# rs232_24V_step_Vano.net
KiCad netlist of a schematic drawn in Altium Designer
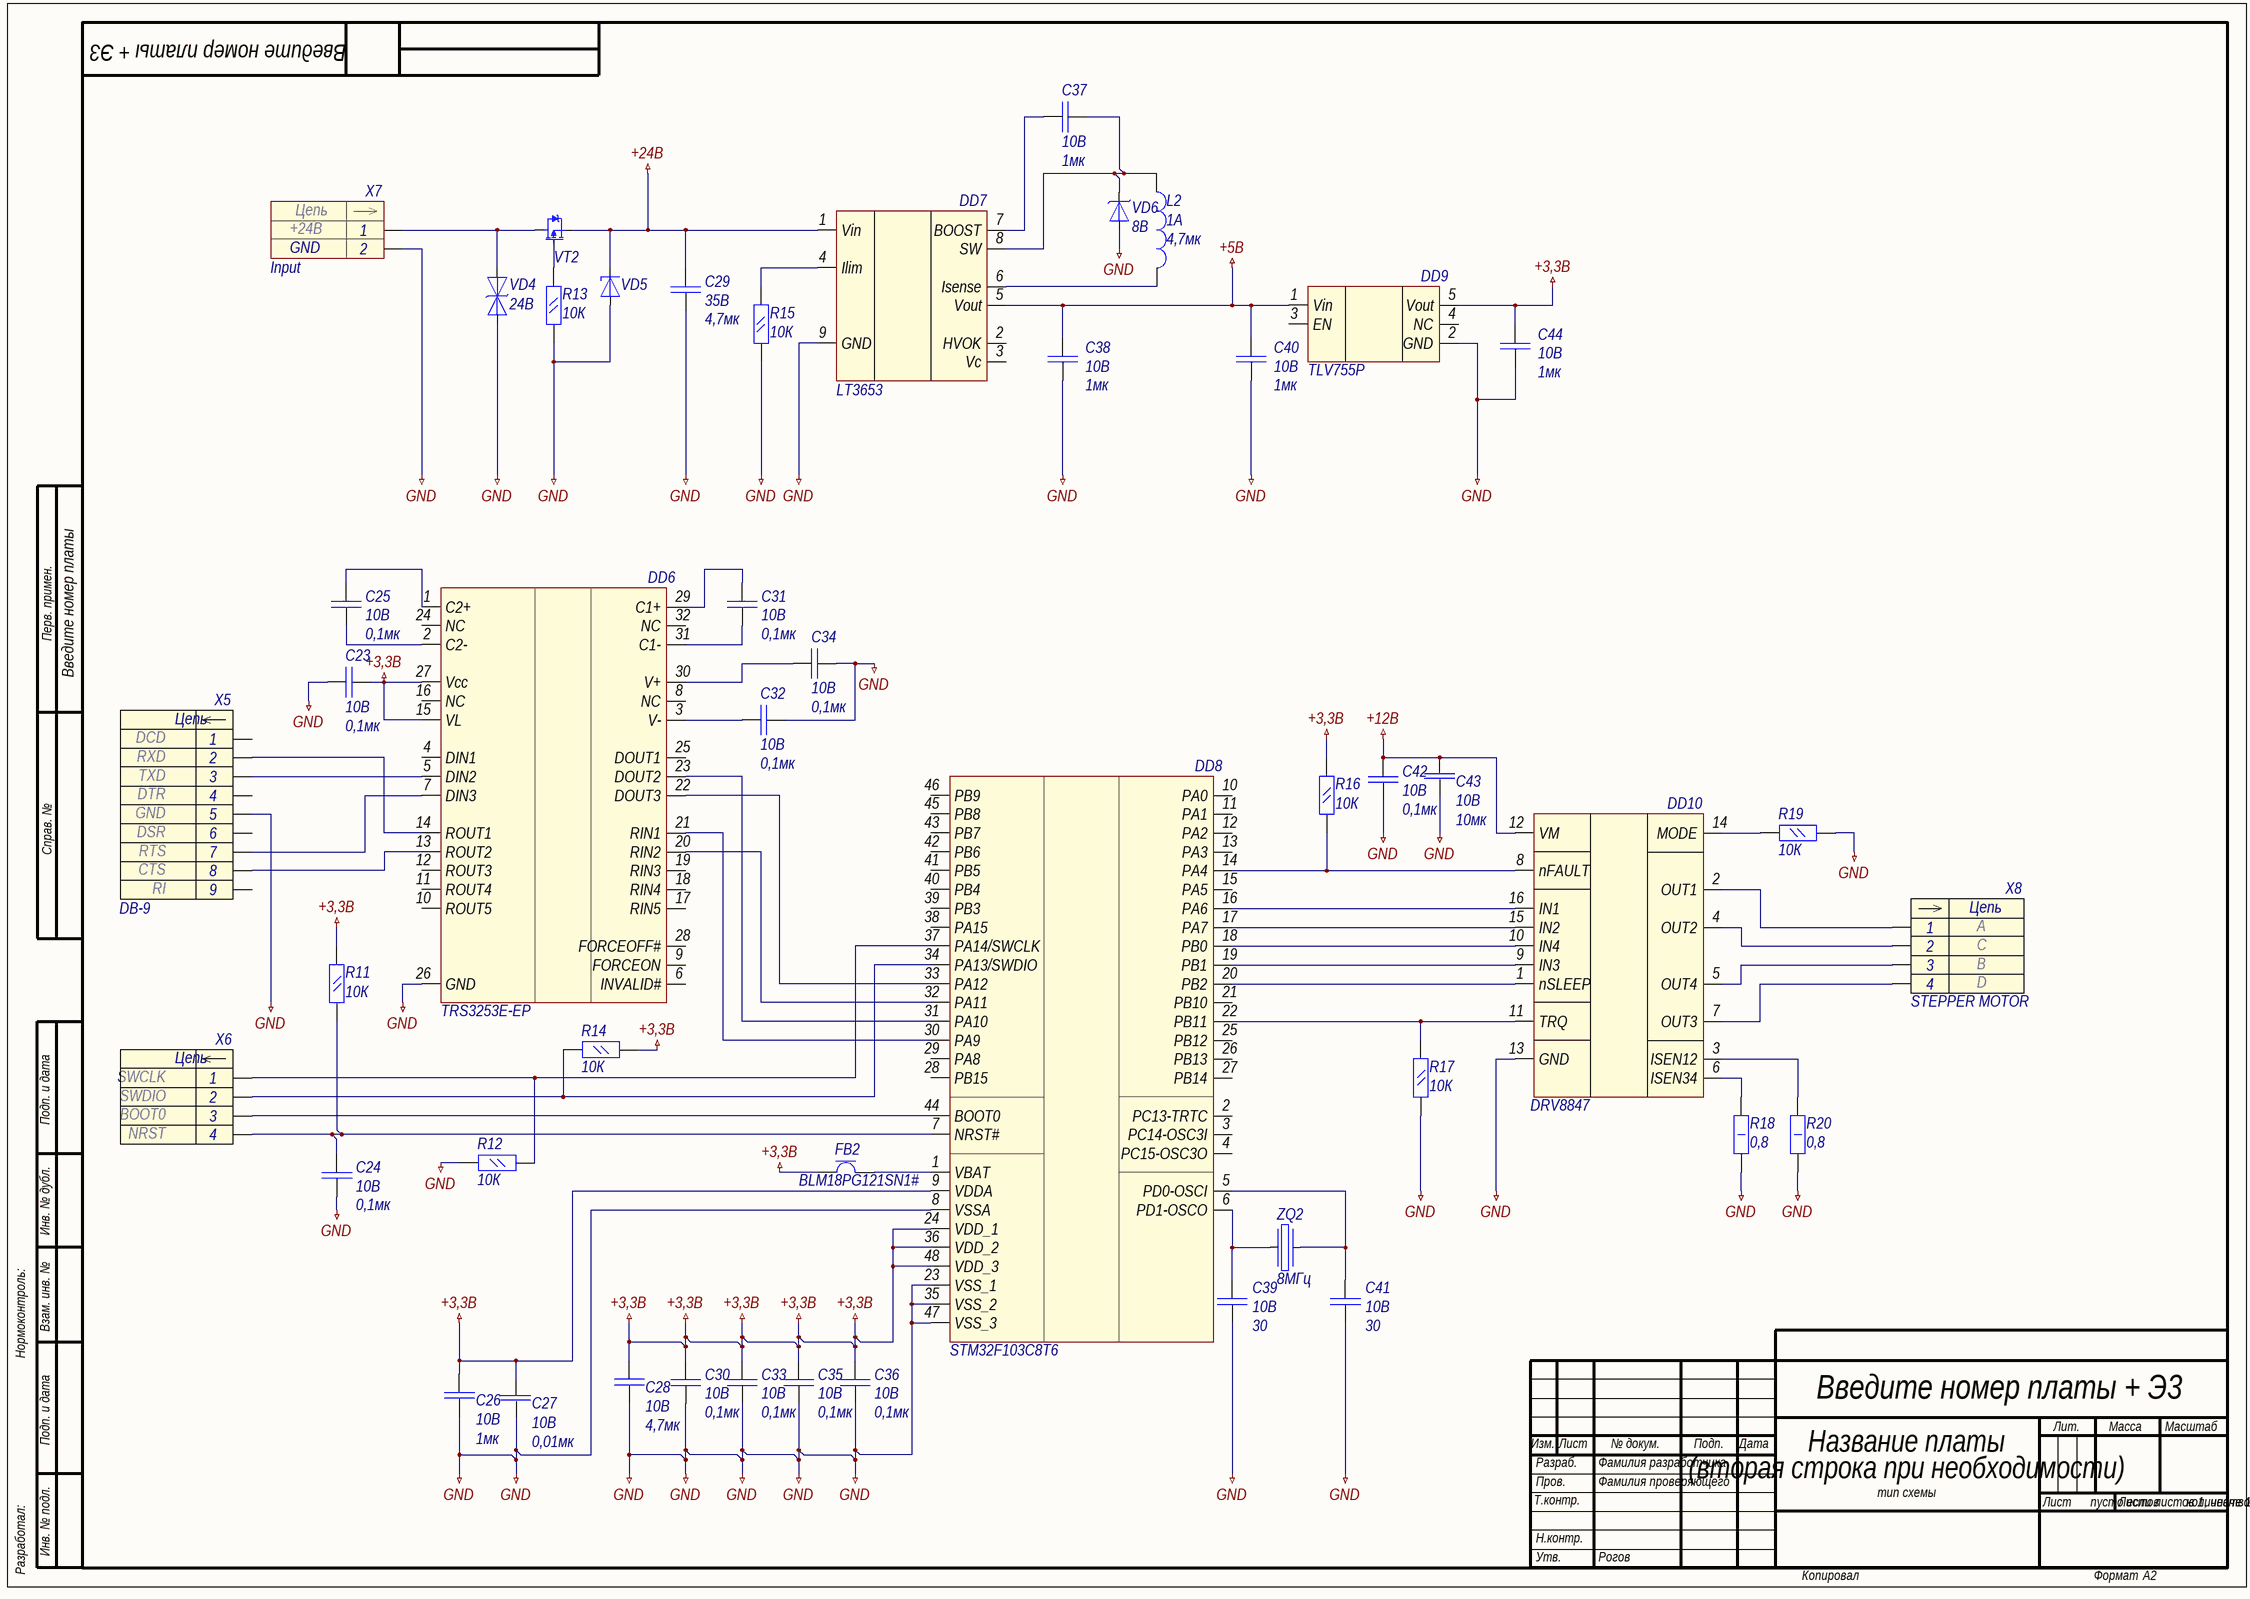
[diagram p0: rs232_24V_step_Vano.SchDoc]

(export (version "E")
  (design (tool "Eeschema 10.0.6"))
  (components
    (comp (ref "C23")
      (value "Capacitor")
      (footprint "CH0402C")
      (fields (field (name "VOLTAGE") "10В") (field (name "CAPACITANCE") "0,1мк"))
      (libsource (lib "GOST_Capacitors") (part "Capacitor"))
    )
    (comp (ref "C24")
      (value "Capacitor")
      (footprint "CH0402C")
      (fields (field (name "VOLTAGE") "10В") (field (name "CAPACITANCE") "0,1мк"))
      (libsource (lib "GOST_Capacitors") (part "Capacitor"))
    )
    (comp (ref "C25")
      (value "Capacitor")
      (footprint "CH0402C")
      (fields (field (name "VOLTAGE") "10В") (field (name "CAPACITANCE") "0,1мк"))
      (libsource (lib "GOST_Capacitors") (part "Capacitor"))
    )
    (comp (ref "C26")
      (value "Capacitor")
      (footprint "CH0201C")
      (fields (field (name "VOLTAGE") "10В") (field (name "CAPACITANCE") "1мк"))
      (libsource (lib "GOST_Capacitors") (part "Capacitor"))
    )
    (comp (ref "C27")
      (value "Capacitor")
      (footprint "CH0402C")
      (fields (field (name "VOLTAGE") "10В") (field (name "CAPACITANCE") "0,01мк"))
      (libsource (lib "") (part "Capacitor_1"))
    )
    (comp (ref "C28")
      (value "Capacitor")
      (footprint "CH0402C")
      (fields (field (name "VOLTAGE") "10В") (field (name "CAPACITANCE") "4,7мк"))
      (libsource (lib "GOST_Capacitors") (part "Capacitor"))
    )
    (comp (ref "C29")
      (value "Capacitor")
      (footprint "CH0603C")
      (fields (field (name "VOLTAGE") "35В") (field (name "CAPACITANCE") "4,7мк"))
      (libsource (lib "GOST_Capacitors") (part "Capacitor"))
    )
    (comp (ref "C30")
      (value "Capacitor")
      (footprint "CH0402C")
      (fields (field (name "VOLTAGE") "10В") (field (name "CAPACITANCE") "0,1мк"))
      (libsource (lib "GOST_Capacitors") (part "Capacitor"))
    )
    (comp (ref "C31")
      (value "Capacitor")
      (footprint "CH0402C")
      (fields (field (name "VOLTAGE") "10В") (field (name "CAPACITANCE") "0,1мк"))
      (libsource (lib "GOST_Capacitors") (part "Capacitor"))
    )
    (comp (ref "C32")
      (value "Capacitor")
      (footprint "CH0402C")
      (fields (field (name "VOLTAGE") "10В") (field (name "CAPACITANCE") "0,1мк"))
      (libsource (lib "GOST_Capacitors") (part "Capacitor"))
    )
    (comp (ref "C33")
      (value "Capacitor")
      (footprint "CH0402C")
      (fields (field (name "VOLTAGE") "10В") (field (name "CAPACITANCE") "0,1мк"))
      (libsource (lib "GOST_Capacitors") (part "Capacitor"))
    )
    (comp (ref "C34")
      (value "Capacitor")
      (footprint "CH0402C")
      (fields (field (name "VOLTAGE") "10В") (field (name "CAPACITANCE") "0,1мк"))
      (libsource (lib "GOST_Capacitors") (part "Capacitor"))
    )
    (comp (ref "C35")
      (value "Capacitor")
      (footprint "CH0402C")
      (fields (field (name "VOLTAGE") "10В") (field (name "CAPACITANCE") "0,1мк"))
      (libsource (lib "GOST_Capacitors") (part "Capacitor"))
    )
    (comp (ref "C36")
      (value "Capacitor")
      (footprint "CH0402C")
      (fields (field (name "VOLTAGE") "10В") (field (name "CAPACITANCE") "0,1мк"))
      (libsource (lib "GOST_Capacitors") (part "Capacitor"))
    )
    (comp (ref "C37")
      (value "Capacitor")
      (footprint "CH0201C")
      (fields (field (name "VOLTAGE") "10В") (field (name "CAPACITANCE") "1мк"))
      (libsource (lib "GOST_Capacitors") (part "Capacitor"))
    )
    (comp (ref "C38")
      (value "Capacitor")
      (footprint "CH0201C")
      (fields (field (name "VOLTAGE") "10В") (field (name "CAPACITANCE") "1мк"))
      (libsource (lib "GOST_Capacitors") (part "Capacitor"))
    )
    (comp (ref "C39")
      (value "Capacitor")
      (footprint "CH0201C")
      (fields (field (name "VOLTAGE") "10В") (field (name "CAPACITANCE") "30"))
      (libsource (lib "GOST_Capacitors") (part "Capacitor"))
    )
    (comp (ref "C40")
      (value "Capacitor")
      (footprint "CH0201C")
      (fields (field (name "VOLTAGE") "10В") (field (name "CAPACITANCE") "1мк"))
      (libsource (lib "GOST_Capacitors") (part "Capacitor"))
    )
    (comp (ref "C41")
      (value "Capacitor")
      (footprint "CH0201C")
      (fields (field (name "VOLTAGE") "10В") (field (name "CAPACITANCE") "30"))
      (libsource (lib "GOST_Capacitors") (part "Capacitor"))
    )
    (comp (ref "C42")
      (value "Capacitor")
      (footprint "CH0402C")
      (fields (field (name "VOLTAGE") "10В") (field (name "CAPACITANCE") "0,1мк"))
      (libsource (lib "GOST_Capacitors") (part "Capacitor"))
    )
    (comp (ref "C43")
      (value "Capacitor")
      (footprint "CH0402C")
      (fields (field (name "VOLTAGE") "10В") (field (name "CAPACITANCE") "10мк"))
      (libsource (lib "") (part "Capacitor_1"))
    )
    (comp (ref "C44")
      (value "Capacitor")
      (footprint "CH0201C")
      (fields (field (name "VOLTAGE") "10В") (field (name "CAPACITANCE") "1мк"))
      (libsource (lib "GOST_Capacitors") (part "Capacitor"))
    )
    (comp (ref "DD6")
      (value "TRS3253E-EP")
      (footprint "TRS3253E-EP")
      (description "UART - RS232")
      (libsource (lib "GOST_lib_devices") (part "TRS3253E-EP"))
    )
    (comp (ref "DD7")
      (value "LT3653")
      (footprint "LT3653")
      (description "7.5~30 to 5")
      (libsource (lib "GOST_lib_devices") (part "LT3653"))
    )
    (comp (ref "DD8")
      (value "STM32F103C8T6")
      (footprint "STM32F103 48pins")
      (libsource (lib "GOST_lib_devices") (part "STM32"))
    )
    (comp (ref "DD9")
      (value "TLV755P")
      (footprint "SOT23-5")
      (libsource (lib "GOST_lib_devices") (part "LDO +3.3V"))
    )
    (comp (ref "DD10")
      (value "DRV8847")
      (footprint "DRV8847")
      (libsource (lib "GOST_lib_devices") (part "DRV8847"))
    )
    (comp (ref "FB2")
      (value "Ferrite bead")
      (footprint "CH0603L")
      (fields (field (name "MODEL") "BLM18PG121SN1#"))
      (libsource (lib "GOST_Inductors") (part "Ferrite bead"))
    )
    (comp (ref "L2")
      (value "Inductor")
      (footprint "CH0805L")
      (fields (field (name "MAX CURRENT") "1А") (field (name "INDUCTANCE") "4,7мк"))
      (libsource (lib "GOST_Inductors") (part "Inductor"))
    )
    (comp (ref "R11")
      (value "Res_0.125")
      (footprint "CH0805R")
      (fields (field (name "IMPEDANCE") "10К"))
      (libsource (lib "") (part "Res_0.125_1"))
    )
    (comp (ref "R12")
      (value "Res_0.125")
      (footprint "CH0805R")
      (fields (field (name "IMPEDANCE") "10К"))
      (libsource (lib "") (part "Res_0.125_1"))
    )
    (comp (ref "R13")
      (value "Res_0.125")
      (footprint "CH0402R")
      (fields (field (name "IMPEDANCE") "10К"))
      (libsource (lib "GOST_Resistors") (part "Res_0.125"))
    )
    (comp (ref "R14")
      (value "Res_0.125")
      (footprint "CH0805R")
      (fields (field (name "IMPEDANCE") "10К"))
      (libsource (lib "") (part "Res_0.125_1"))
    )
    (comp (ref "R15")
      (value "Res_0.125")
      (footprint "CH0402R")
      (fields (field (name "IMPEDANCE") "10К"))
      (libsource (lib "GOST_Resistors") (part "Res_0.125"))
    )
    (comp (ref "R16")
      (value "Res_0.125")
      (footprint "CH0402R")
      (fields (field (name "IMPEDANCE") "10К"))
      (libsource (lib "GOST_Resistors") (part "Res_0.125"))
    )
    (comp (ref "R17")
      (value "Res_0.125")
      (footprint "CH0402R")
      (fields (field (name "IMPEDANCE") "10К"))
      (libsource (lib "GOST_Resistors") (part "Res_0.125"))
    )
    (comp (ref "R18")
      (value "Res_1")
      (footprint "CH2010R")
      (fields (field (name "POWER") "1Вт") (field (name "IMPEDANCE") "0,8"))
      (libsource (lib "GOST_Resistors") (part "Res_1"))
    )
    (comp (ref "R19")
      (value "Res_0.125")
      (footprint "CH0402R")
      (fields (field (name "IMPEDANCE") "10К"))
      (libsource (lib "GOST_Resistors") (part "Res_0.125"))
    )
    (comp (ref "R20")
      (value "Res_1")
      (footprint "CH2010R")
      (fields (field (name "POWER") "1Вт") (field (name "IMPEDANCE") "0,8"))
      (libsource (lib "GOST_Resistors") (part "Res_1"))
    )
    (comp (ref "VD4")
      (value "TVS-diod_simmetrical")
      (footprint "standard:SOD323")
      (fields (field (name "MANUFACTURER") "Torex Semiconductor") (field (name "THRESH_VOLTAGE") "24В"))
      (libsource (lib "GOST_Diodes") (part "TVS-diod_simmetrical"))
    )
    (comp (ref "VD5")
      (value "Diod Zener")
      (footprint "standard:SOD123")
      (libsource (lib "GOST_Diodes") (part "Diod Zener"))
    )
    (comp (ref "VD6")
      (value "TVS-diod_directed")
      (footprint "SOD123W")
      (fields (field (name "MANUFACTURER") "Nexperia") (field (name "CLAMPING_VOLTAGE") "8В"))
      (libsource (lib "GOST_Diodes") (part "TVS-diod_directed"))
    )
    (comp (ref "VT2")
      (value "P-Channel")
      (footprint "SOT23_132")
      (libsource (lib "GOST_Transistors") (part "P-Channel"))
    )
    (comp (ref "X5")
      (value "DB-9")
      (footprint "CON: DB-9F")
      (fields
        (field (name "1") "DCD")
        (field (name "2") "RXD")
        (field (name "3") "TXD")
        (field (name "4") "DTR")
        (field (name "5") "GND")
        (field (name "6") "DSR")
        (field (name "7") "RTS")
        (field (name "8") "CTS")
        (field (name "9") "RI")
      )
      (libsource (lib "GOST_lib_connectors") (part "9_pins"))
    )
    (comp (ref "X6")
      (value "4_pins")
      (footprint "CON: CWF-4R")
      (fields
        (field (name "2") "SWDIO")
        (field (name "3") "BOOT0")
        (field (name "1") "SWCLK")
        (field (name "4") "NRST")
      )
      (libsource (lib "") (part "4_pins_1"))
    )
    (comp (ref "X7")
      (value "Input")
      (footprint "CON: 163-179PH-EX")
      (fields (field (name "VCC") "+24В"))
      (libsource (lib "GOST_lib_connectors") (part "2_pins"))
    )
    (comp (ref "X8")
      (value "STEPPER MOTOR")
      (footprint "CON: CWF-4R")
      (description "Bipolar Stepper Motor 200 Step 0.35A 12VDC")
      (fields (field (name "2") "C") (field (name "3") "B") (field (name "1") "A") (field (name "4") "D"))
      (libsource (lib "GOST_lib_connectors") (part "4_pins"))
    )
    (comp (ref "ZQ2")
      (value "Oscillator")
      (footprint "OSC: 5032")
      (fields (field (name "FREQ") "8МГц"))
      (libsource (lib "GOST_Miscelanuious") (part "Oscillator"))
    )
  )
  (nets
    (net (code "1") (name "+3,3В") (class "Default")
      (node (ref "C23") (pin "2") (pinfunction "C1-_2") (pintype "power_in"))
      (node (ref "C26") (pin "2") (pinfunction "C1-_2") (pintype "power_in"))
      (node (ref "C27") (pin "1") (pinfunction "С+_1") (pintype "power_in"))
      (node (ref "C28") (pin "2") (pinfunction "C1-_2") (pintype "power_in"))
      (node (ref "C30") (pin "1") (pinfunction "C1+_1") (pintype "power_in"))
      (node (ref "C33") (pin "1") (pinfunction "C1+_1") (pintype "power_in"))
      (node (ref "C35") (pin "1") (pinfunction "C1+_1") (pintype "power_in"))
      (node (ref "C36") (pin "1") (pinfunction "C1+_1") (pintype "power_in"))
      (node (ref "C44") (pin "1") (pinfunction "C1+_1") (pintype "power_in"))
      (node (ref "DD6") (pin "15") (pinfunction "VL_15") (pintype "power_in"))
      (node (ref "DD6") (pin "27") (pinfunction "Vcc_27") (pintype "power_in"))
      (node (ref "DD8") (pin "24") (pinfunction "VDD_1_24") (pintype "passive"))
      (node (ref "DD8") (pin "36") (pinfunction "VDD_2_36") (pintype "passive"))
      (node (ref "DD8") (pin "48") (pinfunction "VDD_3_48") (pintype "passive"))
      (node (ref "DD8") (pin "9") (pinfunction "VDDA_9") (pintype "passive"))
      (node (ref "DD9") (pin "5") (pinfunction "Vout_5") (pintype "power_in"))
      (node (ref "FB2") (pin "1") (pintype "power_in"))
      (node (ref "R11") (pin "1") (pinfunction "C1-_1") (pintype "power_in"))
      (node (ref "R14") (pin "2") (pinfunction "C1-_2") (pintype "power_in"))
      (node (ref "R16") (pin "1") (pinfunction "1_1") (pintype "power_in"))
    )
    (net (code "2") (name "+5В") (class "Default")
      (node (ref "C38") (pin "1") (pinfunction "C1+_1") (pintype "power_in"))
      (node (ref "C40") (pin "1") (pinfunction "C1+_1") (pintype "power_in"))
      (node (ref "DD7") (pin "5") (pinfunction "Vout_5") (pintype "power_in"))
      (node (ref "DD9") (pin "1") (pinfunction "Vin_1") (pintype "power_in"))
    )
    (net (code "3") (name "+12В") (class "Default")
      (node (ref "C42") (pin "1") (pinfunction "C1+_1") (pintype "power_in"))
      (node (ref "C43") (pin "1") (pinfunction "С+_1") (pintype "power_in"))
      (node (ref "DD10") (pin "12") (pinfunction "VM_12") (pintype "power_in"))
    )
    (net (code "4") (name "+24В") (class "Default")
      (node (ref "C29") (pin "1") (pinfunction "C1+_1") (pintype "power_in"))
      (node (ref "DD7") (pin "1") (pinfunction "Vin_1") (pintype "power_in"))
      (node (ref "VD5") (pin "2") (pinfunction "C_2") (pintype "passive"))
      (node (ref "VT2") (pin "3") (pinfunction "S_3") (pintype "passive"))
    )
    (net (code "5") (name "GND") (class "Default")
      (node (ref "C23") (pin "1") (pinfunction "C1+_1") (pintype "power_in"))
      (node (ref "C24") (pin "2") (pinfunction "C1-_2") (pintype "power_in"))
      (node (ref "C26") (pin "1") (pinfunction "C1+_1") (pintype "power_in"))
      (node (ref "C27") (pin "2") (pinfunction "С-_2") (pintype "power_in"))
      (node (ref "C28") (pin "1") (pinfunction "C1+_1") (pintype "power_in"))
      (node (ref "C29") (pin "2") (pinfunction "C1-_2") (pintype "power_in"))
      (node (ref "C30") (pin "2") (pinfunction "C1-_2") (pintype "power_in"))
      (node (ref "C32") (pin "2") (pinfunction "C1-_2") (pintype "power_in"))
      (node (ref "C33") (pin "2") (pinfunction "C1-_2") (pintype "power_in"))
      (node (ref "C34") (pin "2") (pinfunction "C1-_2") (pintype "power_in"))
      (node (ref "C35") (pin "2") (pinfunction "C1-_2") (pintype "power_in"))
      (node (ref "C36") (pin "2") (pinfunction "C1-_2") (pintype "power_in"))
      (node (ref "C38") (pin "2") (pinfunction "C1-_2") (pintype "power_in"))
      (node (ref "C39") (pin "2") (pinfunction "C1-_2") (pintype "power_in"))
      (node (ref "C40") (pin "2") (pinfunction "C1-_2") (pintype "power_in"))
      (node (ref "C41") (pin "2") (pinfunction "C1-_2") (pintype "power_in"))
      (node (ref "C42") (pin "2") (pinfunction "C1-_2") (pintype "power_in"))
      (node (ref "C43") (pin "2") (pinfunction "С-_2") (pintype "power_in"))
      (node (ref "C44") (pin "2") (pinfunction "C1-_2") (pintype "power_in"))
      (node (ref "DD10") (pin "13") (pinfunction "GND_13") (pintype "power_in"))
      (node (ref "DD6") (pin "26") (pinfunction "GND_26") (pintype "power_in"))
      (node (ref "DD7") (pin "9") (pinfunction "GND_9") (pintype "power_in"))
      (node (ref "DD8") (pin "23") (pinfunction "VSS_1_23") (pintype "passive"))
      (node (ref "DD8") (pin "35") (pinfunction "VSS_2_35") (pintype "passive"))
      (node (ref "DD8") (pin "47") (pinfunction "VSS_3_47") (pintype "passive"))
      (node (ref "DD8") (pin "8") (pinfunction "VSSA_8") (pintype "passive"))
      (node (ref "DD9") (pin "2") (pinfunction "GND_2") (pintype "power_in"))
      (node (ref "R12") (pin "1") (pinfunction "C1-_1") (pintype "power_in"))
      (node (ref "R13") (pin "1") (pinfunction "1_1") (pintype "power_in"))
      (node (ref "R15") (pin "1") (pinfunction "1_1") (pintype "power_in"))
      (node (ref "R17") (pin "2") (pinfunction "2_2") (pintype "power_in"))
      (node (ref "R18") (pin "1") (pinfunction "*_1") (pintype "power_in"))
      (node (ref "R19") (pin "1") (pinfunction "1_1") (pintype "power_in"))
      (node (ref "R20") (pin "1") (pinfunction "*_1") (pintype "power_in"))
      (node (ref "VD4") (pin "1") (pinfunction "A_1") (pintype "passive"))
      (node (ref "VD5") (pin "1") (pinfunction "A_1") (pintype "passive"))
      (node (ref "VD6") (pin "1") (pinfunction "A_1") (pintype "passive"))
      (node (ref "X5") (pin "5") (pinfunction "5_5") (pintype "passive"))
      (node (ref "X7") (pin "2") (pinfunction "2_2") (pintype "passive"))
    )
    (net (code "6") (name "Net-(C24-C1+)") (class "Default")
      (node (ref "C24") (pin "1") (pinfunction "C1+_1") (pintype "power_in"))
      (node (ref "DD8") (pin "7") (pinfunction "NRST#_7") (pintype "passive"))
      (node (ref "R11") (pin "2") (pinfunction "C1-_2") (pintype "power_in"))
      (node (ref "X6") (pin "4") (pinfunction "4_4") (pintype "passive"))
    )
    (net (code "7") (name "Net-(C25-C1+)") (class "Default")
      (node (ref "C25") (pin "1") (pinfunction "C1+_1") (pintype "power_in"))
      (node (ref "DD6") (pin "1") (pinfunction "C2+_1") (pintype "power_in"))
    )
    (net (code "8") (name "Net-(C25-C1-)") (class "Default")
      (node (ref "C25") (pin "2") (pinfunction "C1-_2") (pintype "power_in"))
      (node (ref "DD6") (pin "2") (pinfunction "C2-_2") (pintype "power_in"))
    )
    (net (code "9") (name "Net-(C31-C1+)") (class "Default")
      (node (ref "C31") (pin "1") (pinfunction "C1+_1") (pintype "power_in"))
      (node (ref "DD6") (pin "29") (pinfunction "C1+_29") (pintype "power_in"))
    )
    (net (code "10") (name "Net-(C31-C1-)") (class "Default")
      (node (ref "C31") (pin "2") (pinfunction "C1-_2") (pintype "power_in"))
      (node (ref "DD6") (pin "31") (pinfunction "C1-_31") (pintype "power_in"))
    )
    (net (code "11") (name "Net-(C32-C1+)") (class "Default")
      (node (ref "C32") (pin "1") (pinfunction "C1+_1") (pintype "power_in"))
      (node (ref "DD6") (pin "3") (pinfunction "V-_3") (pintype "power_in"))
    )
    (net (code "12") (name "Net-(C34-C1+)") (class "Default")
      (node (ref "C34") (pin "1") (pinfunction "C1+_1") (pintype "power_in"))
      (node (ref "DD6") (pin "30") (pinfunction "V+_30") (pintype "power_in"))
    )
    (net (code "13") (name "Net-(C37-C1+)") (class "Default")
      (node (ref "C37") (pin "1") (pinfunction "C1+_1") (pintype "power_in"))
      (node (ref "DD7") (pin "7") (pinfunction "BOOST_7") (pintype "power_in"))
    )
    (net (code "14") (name "Net-(C37-C1-)") (class "Default")
      (node (ref "C37") (pin "2") (pinfunction "C1-_2") (pintype "power_in"))
      (node (ref "DD7") (pin "8") (pinfunction "SW_8") (pintype "power_in"))
      (node (ref "L2") (pin "1") (pinfunction "1_1") (pintype "power_in"))
      (node (ref "VD6") (pin "2") (pinfunction "C_2") (pintype "passive"))
    )
    (net (code "15") (name "Net-(C39-C1+)") (class "Default")
      (node (ref "C39") (pin "1") (pinfunction "C1+_1") (pintype "power_in"))
      (node (ref "DD8") (pin "6") (pinfunction "PD1-OSCO_6") (pintype "passive"))
      (node (ref "ZQ2") (pin "1") (pintype "passive"))
    )
    (net (code "16") (name "Net-(C41-C1+)") (class "Default")
      (node (ref "C41") (pin "1") (pinfunction "C1+_1") (pintype "power_in"))
      (node (ref "DD8") (pin "5") (pinfunction "PD0-OSCI_5") (pintype "passive"))
      (node (ref "ZQ2") (pin "3") (pintype "passive"))
    )
    (net (code "17") (name "Net-(DD6-DIN2)") (class "Default")
      (node (ref "DD6") (pin "5") (pinfunction "DIN2_5") (pintype "power_in"))
      (node (ref "X5") (pin "3") (pinfunction "3_3") (pintype "passive"))
    )
    (net (code "18") (name "Net-(DD6-DIN3)") (class "Default")
      (node (ref "DD6") (pin "7") (pinfunction "DIN3_7") (pintype "power_in"))
      (node (ref "X5") (pin "7") (pinfunction "7_7") (pintype "power_in"))
    )
    (net (code "19") (name "Net-(DD6-DOUT2)") (class "Default")
      (node (ref "DD6") (pin "23") (pinfunction "DOUT2_23") (pintype "power_in"))
      (node (ref "DD8") (pin "31") (pinfunction "PA10_31") (pintype "passive"))
    )
    (net (code "20") (name "Net-(DD6-DOUT3)") (class "Default")
      (node (ref "DD6") (pin "22") (pinfunction "DOUT3_22") (pintype "power_in"))
      (node (ref "DD8") (pin "33") (pinfunction "PA12_33") (pintype "passive"))
    )
    (net (code "21") (name "Net-(DD6-RIN1)") (class "Default")
      (node (ref "DD6") (pin "21") (pinfunction "RIN1_21") (pintype "power_in"))
      (node (ref "DD8") (pin "30") (pinfunction "PA9_30") (pintype "passive"))
    )
    (net (code "22") (name "Net-(DD6-RIN2)") (class "Default")
      (node (ref "DD6") (pin "20") (pinfunction "RIN2_20") (pintype "power_in"))
      (node (ref "DD8") (pin "32") (pinfunction "PA11_32") (pintype "passive"))
    )
    (net (code "23") (name "Net-(DD6-ROUT1)") (class "Default")
      (node (ref "DD6") (pin "14") (pinfunction "ROUT1_14") (pintype "power_in"))
      (node (ref "X5") (pin "2") (pinfunction "2_2") (pintype "passive"))
    )
    (net (code "24") (name "Net-(DD6-ROUT2)") (class "Default")
      (node (ref "DD6") (pin "13") (pinfunction "ROUT2_13") (pintype "power_in"))
      (node (ref "X5") (pin "8") (pinfunction "8_8") (pintype "power_in"))
    )
    (net (code "25") (name "Net-(DD7-Ilim)") (class "Default")
      (node (ref "DD7") (pin "4") (pinfunction "Ilim_4") (pintype "power_in"))
      (node (ref "R15") (pin "2") (pinfunction "2_2") (pintype "power_in"))
    )
    (net (code "26") (name "Net-(DD7-Isense)") (class "Default")
      (node (ref "DD7") (pin "6") (pinfunction "Isense_6") (pintype "power_in"))
      (node (ref "L2") (pin "2") (pinfunction "2_2") (pintype "power_in"))
    )
    (net (code "27") (name "Net-(DD8-BOOT0)") (class "Default")
      (node (ref "DD8") (pin "44") (pinfunction "BOOT0_44") (pintype "passive"))
      (node (ref "X6") (pin "3") (pinfunction "3_3") (pintype "passive"))
    )
    (net (code "28") (name "Net-(DD8-PA13{slash}SWDIO)") (class "Default")
      (node (ref "DD8") (pin "34") (pinfunction "PA13/SWDIO_34") (pintype "passive"))
      (node (ref "R14") (pin "1") (pinfunction "C1-_1") (pintype "power_in"))
      (node (ref "X6") (pin "2") (pinfunction "2_2") (pintype "passive"))
    )
    (net (code "29") (name "Net-(DD8-PA14{slash}SWCLK)") (class "Default")
      (node (ref "DD8") (pin "37") (pinfunction "PA14/SWCLK_37") (pintype "passive"))
      (node (ref "R12") (pin "2") (pinfunction "C1-_2") (pintype "power_in"))
      (node (ref "X6") (pin "1") (pinfunction "1_1") (pintype "passive"))
    )
    (net (code "30") (name "Net-(DD8-VBAT)") (class "Default")
      (node (ref "DD8") (pin "1") (pinfunction "VBAT_1") (pintype "passive"))
      (node (ref "FB2") (pin "2") (pintype "power_in"))
    )
    (net (code "31") (name "Net-(DD10-IN1)") (class "Default")
      (node (ref "DD10") (pin "16") (pinfunction "IN1_16") (pintype "power_in"))
      (node (ref "DD8") (pin "16") (pinfunction "PA6_16") (pintype "passive"))
    )
    (net (code "32") (name "Net-(DD10-IN2)") (class "Default")
      (node (ref "DD10") (pin "15") (pinfunction "IN2_15") (pintype "power_in"))
      (node (ref "DD8") (pin "17") (pinfunction "PA7_17") (pintype "passive"))
    )
    (net (code "33") (name "Net-(DD10-IN3)") (class "Default")
      (node (ref "DD10") (pin "9") (pinfunction "IN3_9") (pintype "power_in"))
      (node (ref "DD8") (pin "19") (pinfunction "PB1_19") (pintype "passive"))
    )
    (net (code "34") (name "Net-(DD10-IN4)") (class "Default")
      (node (ref "DD10") (pin "10") (pinfunction "IN4_10") (pintype "power_in"))
      (node (ref "DD8") (pin "18") (pinfunction "PB0_18") (pintype "passive"))
    )
    (net (code "35") (name "Net-(DD10-ISEN12)") (class "Default")
      (node (ref "DD10") (pin "3") (pinfunction "ISEN12_3") (pintype "power_in"))
      (node (ref "R20") (pin "2") (pinfunction "*_2") (pintype "power_in"))
    )
    (net (code "36") (name "Net-(DD10-ISEN34)") (class "Default")
      (node (ref "DD10") (pin "6") (pinfunction "ISEN34_6") (pintype "power_in"))
      (node (ref "R18") (pin "2") (pinfunction "*_2") (pintype "power_in"))
    )
    (net (code "37") (name "Net-(DD10-MODE)") (class "Default")
      (node (ref "DD10") (pin "14") (pinfunction "MODE_14") (pintype "power_in"))
      (node (ref "R19") (pin "2") (pinfunction "2_2") (pintype "power_in"))
    )
    (net (code "38") (name "Net-(DD10-OUT1)") (class "Default")
      (node (ref "DD10") (pin "2") (pinfunction "OUT1_2") (pintype "power_in"))
      (node (ref "X8") (pin "1") (pinfunction "1_1") (pintype "passive"))
    )
    (net (code "39") (name "Net-(DD10-OUT2)") (class "Default")
      (node (ref "DD10") (pin "4") (pinfunction "OUT2_4") (pintype "power_in"))
      (node (ref "X8") (pin "2") (pinfunction "2_2") (pintype "passive"))
    )
    (net (code "40") (name "Net-(DD10-OUT3)") (class "Default")
      (node (ref "DD10") (pin "7") (pinfunction "OUT3_7") (pintype "power_in"))
      (node (ref "X8") (pin "4") (pinfunction "4_4") (pintype "passive"))
    )
    (net (code "41") (name "Net-(DD10-OUT4)") (class "Default")
      (node (ref "DD10") (pin "5") (pinfunction "OUT4_5") (pintype "power_in"))
      (node (ref "X8") (pin "3") (pinfunction "3_3") (pintype "passive"))
    )
    (net (code "42") (name "Net-(DD10-TRQ)") (class "Default")
      (node (ref "DD10") (pin "11") (pinfunction "TRQ_11") (pintype "power_in"))
      (node (ref "DD8") (pin "22") (pinfunction "PB11_22") (pintype "passive"))
      (node (ref "R17") (pin "1") (pinfunction "1_1") (pintype "power_in"))
    )
    (net (code "43") (name "Net-(DD10-nFAULT)") (class "Default")
      (node (ref "DD10") (pin "8") (pinfunction "nFAULT_8") (pintype "power_in"))
      (node (ref "DD8") (pin "14") (pinfunction "PA4_14") (pintype "passive"))
      (node (ref "R16") (pin "2") (pinfunction "2_2") (pintype "power_in"))
    )
    (net (code "44") (name "Net-(DD10-nSLEEP)") (class "Default")
      (node (ref "DD10") (pin "1") (pinfunction "nSLEEP_1") (pintype "power_in"))
      (node (ref "DD8") (pin "20") (pinfunction "PB2_20") (pintype "passive"))
    )
    (net (code "45") (name "Net-(VD4-C)") (class "Default")
      (node (ref "VD4") (pin "2") (pinfunction "C_2") (pintype "passive"))
      (node (ref "VT2") (pin "2") (pinfunction "D_2") (pintype "passive"))
      (node (ref "X7") (pin "1") (pinfunction "1_1") (pintype "passive"))
    )
    (net (code "46") (name "Net-(VT2-G)") (class "Default")
      (node (ref "R13") (pin "2") (pinfunction "2_2") (pintype "power_in"))
      (node (ref "VT2") (pin "1") (pinfunction "G_1") (pintype "passive"))
    )
    (net (code "47") (name "unconnected-(DD6-DIN1-Pad4)") (class "Default")
      (node (ref "DD6") (pin "4") (pinfunction "DIN1_4") (pintype "power_in"))
    )
    (net (code "48") (name "unconnected-(DD6-DOUT1-Pad25)") (class "Default")
      (node (ref "DD6") (pin "25") (pinfunction "DOUT1_25") (pintype "power_in"))
    )
    (net (code "49") (name "unconnected-(DD6-FORCEOFF#-Pad28)") (class "Default")
      (node (ref "DD6") (pin "28") (pinfunction "FORCEOFF#_28") (pintype "power_in"))
    )
    (net (code "50") (name "unconnected-(DD6-FORCEON-Pad9)") (class "Default")
      (node (ref "DD6") (pin "9") (pinfunction "FORCEON_9") (pintype "power_in"))
    )
    (net (code "51") (name "unconnected-(DD6-INVALID#-Pad6)") (class "Default")
      (node (ref "DD6") (pin "6") (pinfunction "INVALID#_6") (pintype "power_in"))
    )
    (net (code "52") (name "unconnected-(DD6-NC-Pad8)") (class "Default")
      (node (ref "DD6") (pin "8") (pinfunction "NC_8") (pintype "power_in"))
    )
    (net (code "53") (name "unconnected-(DD6-NC-Pad16)") (class "Default")
      (node (ref "DD6") (pin "16") (pinfunction "NC_16") (pintype "power_in"))
    )
    (net (code "54") (name "unconnected-(DD6-NC-Pad24)") (class "Default")
      (node (ref "DD6") (pin "24") (pinfunction "NC_24") (pintype "power_in"))
    )
    (net (code "55") (name "unconnected-(DD6-NC-Pad32)") (class "Default")
      (node (ref "DD6") (pin "32") (pinfunction "NC_32") (pintype "power_in"))
    )
    (net (code "56") (name "unconnected-(DD6-RIN3-Pad19)") (class "Default")
      (node (ref "DD6") (pin "19") (pinfunction "RIN3_19") (pintype "power_in"))
    )
    (net (code "57") (name "unconnected-(DD6-RIN4-Pad18)") (class "Default")
      (node (ref "DD6") (pin "18") (pinfunction "RIN4_18") (pintype "power_in"))
    )
    (net (code "58") (name "unconnected-(DD6-RIN5-Pad17)") (class "Default")
      (node (ref "DD6") (pin "17") (pinfunction "RIN5_17") (pintype "power_in"))
    )
    (net (code "59") (name "unconnected-(DD6-ROUT3-Pad12)") (class "Default")
      (node (ref "DD6") (pin "12") (pinfunction "ROUT3_12") (pintype "power_in"))
    )
    (net (code "60") (name "unconnected-(DD6-ROUT4-Pad11)") (class "Default")
      (node (ref "DD6") (pin "11") (pinfunction "ROUT4_11") (pintype "power_in"))
    )
    (net (code "61") (name "unconnected-(DD6-ROUT5-Pad10)") (class "Default")
      (node (ref "DD6") (pin "10") (pinfunction "ROUT5_10") (pintype "power_in"))
    )
    (net (code "62") (name "unconnected-(DD7-HVOK-Pad2)") (class "Default")
      (node (ref "DD7") (pin "2") (pinfunction "HVOK_2") (pintype "power_in"))
    )
    (net (code "63") (name "unconnected-(DD7-Vc-Pad3)") (class "Default")
      (node (ref "DD7") (pin "3") (pinfunction "Vc_3") (pintype "power_in"))
    )
    (net (code "64") (name "unconnected-(DD8-PA0-Pad10)") (class "Default")
      (node (ref "DD8") (pin "10") (pinfunction "PA0_10") (pintype "passive"))
    )
    (net (code "65") (name "unconnected-(DD8-PA1-Pad11)") (class "Default")
      (node (ref "DD8") (pin "11") (pinfunction "PA1_11") (pintype "passive"))
    )
    (net (code "66") (name "unconnected-(DD8-PA2-Pad12)") (class "Default")
      (node (ref "DD8") (pin "12") (pinfunction "PA2_12") (pintype "passive"))
    )
    (net (code "67") (name "unconnected-(DD8-PA3-Pad13)") (class "Default")
      (node (ref "DD8") (pin "13") (pinfunction "PA3_13") (pintype "passive"))
    )
    (net (code "68") (name "unconnected-(DD8-PA5-Pad15)") (class "Default")
      (node (ref "DD8") (pin "15") (pinfunction "PA5_15") (pintype "passive"))
    )
    (net (code "69") (name "unconnected-(DD8-PA8-Pad29)") (class "Default")
      (node (ref "DD8") (pin "29") (pinfunction "PA8_29") (pintype "passive"))
    )
    (net (code "70") (name "unconnected-(DD8-PA15-Pad38)") (class "Default")
      (node (ref "DD8") (pin "38") (pinfunction "PA15_38") (pintype "passive"))
    )
    (net (code "71") (name "unconnected-(DD8-PB3-Pad39)") (class "Default")
      (node (ref "DD8") (pin "39") (pinfunction "PB3_39") (pintype "passive"))
    )
    (net (code "72") (name "unconnected-(DD8-PB4-Pad40)") (class "Default")
      (node (ref "DD8") (pin "40") (pinfunction "PB4_40") (pintype "passive"))
    )
    (net (code "73") (name "unconnected-(DD8-PB5-Pad41)") (class "Default")
      (node (ref "DD8") (pin "41") (pinfunction "PB5_41") (pintype "passive"))
    )
    (net (code "74") (name "unconnected-(DD8-PB6-Pad42)") (class "Default")
      (node (ref "DD8") (pin "42") (pinfunction "PB6_42") (pintype "passive"))
    )
    (net (code "75") (name "unconnected-(DD8-PB7-Pad43)") (class "Default")
      (node (ref "DD8") (pin "43") (pinfunction "PB7_43") (pintype "passive"))
    )
    (net (code "76") (name "unconnected-(DD8-PB8-Pad45)") (class "Default")
      (node (ref "DD8") (pin "45") (pinfunction "PB8_45") (pintype "passive"))
    )
    (net (code "77") (name "unconnected-(DD8-PB9-Pad46)") (class "Default")
      (node (ref "DD8") (pin "46") (pinfunction "PB9_46") (pintype "passive"))
    )
    (net (code "78") (name "unconnected-(DD8-PB10-Pad21)") (class "Default")
      (node (ref "DD8") (pin "21") (pinfunction "PB10_21") (pintype "passive"))
    )
    (net (code "79") (name "unconnected-(DD8-PB12-Pad25)") (class "Default")
      (node (ref "DD8") (pin "25") (pinfunction "PB12_25") (pintype "passive"))
    )
    (net (code "80") (name "unconnected-(DD8-PB13-Pad26)") (class "Default")
      (node (ref "DD8") (pin "26") (pinfunction "PB13_26") (pintype "passive"))
    )
    (net (code "81") (name "unconnected-(DD8-PB14-Pad27)") (class "Default")
      (node (ref "DD8") (pin "27") (pinfunction "PB14_27") (pintype "passive"))
    )
    (net (code "82") (name "unconnected-(DD8-PB15-Pad28)") (class "Default")
      (node (ref "DD8") (pin "28") (pinfunction "PB15_28") (pintype "passive"))
    )
    (net (code "83") (name "unconnected-(DD8-PC13-TRTC-Pad2)") (class "Default")
      (node (ref "DD8") (pin "2") (pinfunction "PC13-TRTC_2") (pintype "passive"))
    )
    (net (code "84") (name "unconnected-(DD8-PC14-OSC3I-Pad3)") (class "Default")
      (node (ref "DD8") (pin "3") (pinfunction "PC14-OSC3I_3") (pintype "passive"))
    )
    (net (code "85") (name "unconnected-(DD8-PC15-OSC3O-Pad4)") (class "Default")
      (node (ref "DD8") (pin "4") (pinfunction "PC15-OSC3O_4") (pintype "passive"))
    )
    (net (code "86") (name "unconnected-(DD9-EN-Pad3)") (class "Default")
      (node (ref "DD9") (pin "3") (pinfunction "EN_3") (pintype "power_in"))
    )
    (net (code "87") (name "unconnected-(DD9-NC-Pad4)") (class "Default")
      (node (ref "DD9") (pin "4") (pinfunction "NC_4") (pintype "power_in"))
    )
    (net (code "88") (name "unconnected-(X5-Pad1)") (class "Default")
      (node (ref "X5") (pin "1") (pinfunction "1_1") (pintype "passive"))
    )
    (net (code "89") (name "unconnected-(X5-Pad4)") (class "Default")
      (node (ref "X5") (pin "4") (pinfunction "4_4") (pintype "passive"))
    )
    (net (code "90") (name "unconnected-(X5-Pad6)") (class "Default")
      (node (ref "X5") (pin "6") (pinfunction "6_6") (pintype "passive"))
    )
    (net (code "91") (name "unconnected-(X5-Pad9)") (class "Default")
      (node (ref "X5") (pin "9") (pinfunction "9_9") (pintype "power_in"))
    )
  )
)
